# Sheet1_Filter.net
KiCad netlist of a schematic drawn in Altium Designer
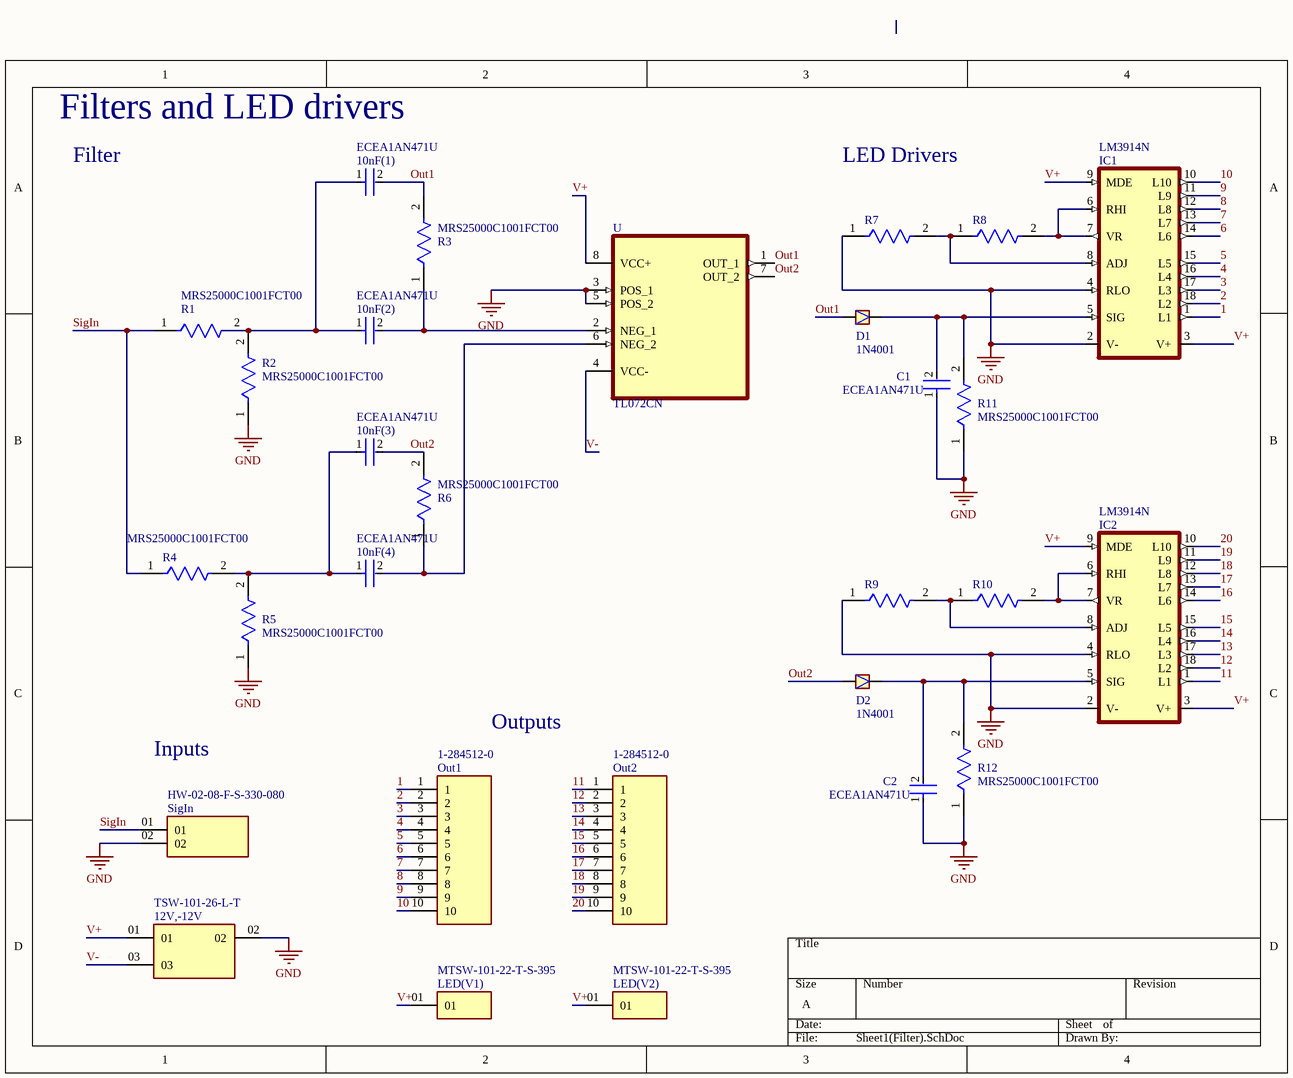
[diagram p0: Sheet1(Filter).SchDoc]

(export (version "E")
  (design (tool "Eeschema 10.0.6"))
  (components
    (comp (ref "10nF(1)")
      (value "ECEA1AN471U")
      (footprint "FP-RAD-TH-D_10_0_5-L_16_1-MFG")
      (description "Aluminum Electrolytic Capacitors (Radial Lead Type) 470uF ±20% 10V")
      (fields (field (name "TOLERANCE") "20%") (field (name "VOLTAGE") "10V"))
      (libsource (lib "Altium Content Vault") (part "02cd4be3c70576c341d710602a673aa"))
    )
    (comp (ref "10nF(2)")
      (value "ECEA1AN471U")
      (footprint "FP-RAD-TH-D_10_0_5-L_16_1-MFG")
      (description "Aluminum Electrolytic Capacitors (Radial Lead Type) 470uF ±20% 10V")
      (fields (field (name "TOLERANCE") "20%") (field (name "VOLTAGE") "10V"))
      (libsource (lib "Altium Content Vault") (part "02cd4be3c70576c341d710602a673aa"))
    )
    (comp (ref "10nF(3)")
      (value "ECEA1AN471U")
      (footprint "FP-RAD-TH-D_10_0_5-L_16_1-MFG")
      (description "Aluminum Electrolytic Capacitors (Radial Lead Type) 470uF ±20% 10V")
      (fields (field (name "TOLERANCE") "20%") (field (name "VOLTAGE") "10V"))
      (libsource (lib "Altium Content Vault") (part "02cd4be3c70576c341d710602a673aa"))
    )
    (comp (ref "10nF(4)")
      (value "ECEA1AN471U")
      (footprint "FP-RAD-TH-D_10_0_5-L_16_1-MFG")
      (description "Aluminum Electrolytic Capacitors (Radial Lead Type) 470uF ±20% 10V")
      (fields (field (name "TOLERANCE") "20%") (field (name "VOLTAGE") "10V"))
      (libsource (lib "Altium Content Vault") (part "02cd4be3c70576c341d710602a673aa"))
    )
    (comp (ref "12V,-12V")
      (value "TSW-101-26-L-T")
      (footprint "SAMTEC_TSW-101-26-L-T")
      (libsource (lib "TSW-101-26-L-T") (part "TSW-101-26-L-T"))
    )
    (comp (ref "C1")
      (value "ECEA1AN471U")
      (footprint "FP-RAD-TH-D_10_0_5-L_16_1-MFG")
      (description "Aluminum Electrolytic Capacitors (Radial Lead Type) 470uF ±20% 10V")
      (fields (field (name "TOLERANCE") "20%") (field (name "VOLTAGE") "10V"))
      (libsource (lib "Altium Content Vault") (part "02cd4be3c70576c341d710602a673aa"))
    )
    (comp (ref "C2")
      (value "ECEA1AN471U")
      (footprint "FP-RAD-TH-D_10_0_5-L_16_1-MFG")
      (description "Aluminum Electrolytic Capacitors (Radial Lead Type) 470uF ±20% 10V")
      (fields (field (name "TOLERANCE") "20%") (field (name "VOLTAGE") "10V"))
      (libsource (lib "Altium Content Vault") (part "02cd4be3c70576c341d710602a673aa"))
    )
    (comp (ref "D1")
      (value "1N4001")
      (footprint "DO41-10")
      (description "<B>DIODE</B><p> general purpose rectifier, 1 A")
      (fields (field (name "MP") "altium_native_batch"))
      (libsource (lib "1N4001") (part "1N4001"))
    )
    (comp (ref "D2")
      (value "1N4001")
      (footprint "DO41-10")
      (description "<B>DIODE</B><p> general purpose rectifier, 1 A")
      (fields (field (name "MP") "altium_native_batch"))
      (libsource (lib "1N4001") (part "1N4001"))
    )
    (comp (ref "IC1")
      (value "LM3914N")
      (footprint "DIL18")
      (description "LED Lighting Drivers")
      (fields (field (name "MF") "Texas Instruments"))
      (libsource (lib "LM3914N") (part "LM3914N"))
    )
    (comp (ref "IC2")
      (value "LM3914N")
      (footprint "DIL18")
      (description "LED Lighting Drivers")
      (fields (field (name "MF") "Texas Instruments"))
      (libsource (lib "LM3914N") (part "LM3914N"))
    )
    (comp (ref "LED(V1)")
      (value "MTSW-101-22-T-S-395")
      (footprint "SAMTEC_MTSW-101-22-T-S-395")
      (description "Connector Header Through Hole 1 position")
      (fields (field (name "MF") "Samtec"))
      (libsource (lib "MTSW-101-22-T-S-395") (part "MTSW-101-22-T-S-395"))
    )
    (comp (ref "LED(V2)")
      (value "MTSW-101-22-T-S-395")
      (footprint "SAMTEC_MTSW-101-22-T-S-395")
      (description "Connector Header Through Hole 1 position")
      (fields (field (name "MF") "Samtec"))
      (libsource (lib "MTSW-101-22-T-S-395") (part "MTSW-101-22-T-S-395"))
    )
    (comp (ref "Out1")
      (value "1-284512-0")
      (footprint "TE_1-284512-0")
      (description "10 POS TERMI-BLOK HDR 900 POLA")
      (fields (field (name "MF") "TE Connectivity"))
      (libsource (lib "1-284512-0") (part "1-284512-0"))
    )
    (comp (ref "Out2")
      (value "1-284512-0")
      (footprint "TE_1-284512-0")
      (description "10 POS TERMI-BLOK HDR 900 POLA")
      (fields (field (name "MF") "TE Connectivity"))
      (libsource (lib "1-284512-0") (part "1-284512-0"))
    )
    (comp (ref "R1")
      (value "MRS25000C1001FCT00")
      (footprint "FP-MRS25-MFG")
      (description "RES 1K OHM 0.6W 1% AXIAL")
      (fields (field (name "TOLERANCE") "1%"))
      (libsource (lib "Altium Content Vault") (part "1029c3af85768c4190bb7ad29bc67b5"))
    )
    (comp (ref "R2")
      (value "MRS25000C1001FCT00")
      (footprint "FP-MRS25-MFG")
      (description "RES 1K OHM 0.6W 1% AXIAL")
      (fields (field (name "TOLERANCE") "1%"))
      (libsource (lib "Altium Content Vault") (part "1029c3af85768c4190bb7ad29bc67b5"))
    )
    (comp (ref "R3")
      (value "MRS25000C1001FCT00")
      (footprint "FP-MRS25-MFG")
      (description "RES 1K OHM 0.6W 1% AXIAL")
      (fields (field (name "TOLERANCE") "1%"))
      (libsource (lib "Altium Content Vault") (part "1029c3af85768c4190bb7ad29bc67b5"))
    )
    (comp (ref "R4")
      (value "MRS25000C1001FCT00")
      (footprint "FP-MRS25-MFG")
      (description "RES 1K OHM 0.6W 1% AXIAL")
      (fields (field (name "TOLERANCE") "1%"))
      (libsource (lib "Altium Content Vault") (part "1029c3af85768c4190bb7ad29bc67b5"))
    )
    (comp (ref "R5")
      (value "MRS25000C1001FCT00")
      (footprint "FP-MRS25-MFG")
      (description "RES 1K OHM 0.6W 1% AXIAL")
      (fields (field (name "TOLERANCE") "1%"))
      (libsource (lib "Altium Content Vault") (part "1029c3af85768c4190bb7ad29bc67b5"))
    )
    (comp (ref "R6")
      (value "MRS25000C1001FCT00")
      (footprint "FP-MRS25-MFG")
      (description "RES 1K OHM 0.6W 1% AXIAL")
      (fields (field (name "TOLERANCE") "1%"))
      (libsource (lib "Altium Content Vault") (part "1029c3af85768c4190bb7ad29bc67b5"))
    )
    (comp (ref "R7")
      (value "MRS25000C1001FCT00")
      (footprint "FP-MRS25-MFG")
      (description "RES 1K OHM 0.6W 1% AXIAL")
      (fields (field (name "TOLERANCE") "1%"))
      (libsource (lib "Altium Content Vault") (part "1029c3af85768c4190bb7ad29bc67b5"))
    )
    (comp (ref "R8")
      (value "MRS25000C1001FCT00")
      (footprint "FP-MRS25-MFG")
      (description "RES 1K OHM 0.6W 1% AXIAL")
      (fields (field (name "TOLERANCE") "1%"))
      (libsource (lib "Altium Content Vault") (part "1029c3af85768c4190bb7ad29bc67b5"))
    )
    (comp (ref "R9")
      (value "MRS25000C1001FCT00")
      (footprint "FP-MRS25-MFG")
      (description "RES 1K OHM 0.6W 1% AXIAL")
      (fields (field (name "TOLERANCE") "1%"))
      (libsource (lib "Altium Content Vault") (part "1029c3af85768c4190bb7ad29bc67b5"))
    )
    (comp (ref "R10")
      (value "MRS25000C1001FCT00")
      (footprint "FP-MRS25-MFG")
      (description "RES 1K OHM 0.6W 1% AXIAL")
      (fields (field (name "TOLERANCE") "1%"))
      (libsource (lib "Altium Content Vault") (part "1029c3af85768c4190bb7ad29bc67b5"))
    )
    (comp (ref "R11")
      (value "MRS25000C1001FCT00")
      (footprint "FP-MRS25-MFG")
      (description "RES 1K OHM 0.6W 1% AXIAL")
      (fields (field (name "TOLERANCE") "1%"))
      (libsource (lib "Altium Content Vault") (part "1029c3af85768c4190bb7ad29bc67b5"))
    )
    (comp (ref "R12")
      (value "MRS25000C1001FCT00")
      (footprint "FP-MRS25-MFG")
      (description "RES 1K OHM 0.6W 1% AXIAL")
      (fields (field (name "TOLERANCE") "1%"))
      (libsource (lib "Altium Content Vault") (part "1029c3af85768c4190bb7ad29bc67b5"))
    )
    (comp (ref "SigIn")
      (value "HW-02-08-F-S-330-080")
      (footprint "SAMTEC_HW-02-08-F-S-330-080")
      (libsource (lib "HW-02-08-F-S-330-080") (part "HW-02-08-F-S-330-080"))
    )
    (comp (ref "U")
      (value "TL072CN")
      (footprint "DIP254P762X533-8")
      (description "J-FET Amplifier 2 Circuit 8-DIP")
      (fields (field (name "MF") "Texas Instruments"))
      (libsource (lib "TL072CN") (part "TL072CN"))
    )
  )
  (nets
    (net (code "1") (name "/1") (class "Default")
      (node (ref "IC1") (pin "1") (pinfunction "L1_1") (pintype "output"))
      (node (ref "Out1") (pin "1") (pinfunction "1_1") (pintype "passive"))
    )
    (net (code "2") (name "/2") (class "Default")
      (node (ref "IC1") (pin "18") (pinfunction "L2_18") (pintype "output"))
      (node (ref "Out1") (pin "2") (pinfunction "2_2") (pintype "passive"))
    )
    (net (code "3") (name "/3") (class "Default")
      (node (ref "IC1") (pin "17") (pinfunction "L3_17") (pintype "output"))
      (node (ref "Out1") (pin "3") (pinfunction "3_3") (pintype "passive"))
    )
    (net (code "4") (name "/4") (class "Default")
      (node (ref "IC1") (pin "16") (pinfunction "L4_16") (pintype "output"))
      (node (ref "Out1") (pin "4") (pinfunction "4_4") (pintype "passive"))
    )
    (net (code "5") (name "/5") (class "Default")
      (node (ref "IC1") (pin "15") (pinfunction "L5_15") (pintype "output"))
      (node (ref "Out1") (pin "5") (pinfunction "5_5") (pintype "passive"))
    )
    (net (code "6") (name "/6") (class "Default")
      (node (ref "IC1") (pin "14") (pinfunction "L6_14") (pintype "output"))
      (node (ref "Out1") (pin "6") (pinfunction "6_6") (pintype "passive"))
    )
    (net (code "7") (name "/7") (class "Default")
      (node (ref "IC1") (pin "13") (pinfunction "L7_13") (pintype "output"))
      (node (ref "Out1") (pin "7") (pinfunction "7_7") (pintype "passive"))
    )
    (net (code "8") (name "/8") (class "Default")
      (node (ref "IC1") (pin "12") (pinfunction "L8_12") (pintype "output"))
      (node (ref "Out1") (pin "8") (pinfunction "8_8") (pintype "passive"))
    )
    (net (code "9") (name "/9") (class "Default")
      (node (ref "IC1") (pin "11") (pinfunction "L9_11") (pintype "output"))
      (node (ref "Out1") (pin "9") (pinfunction "9_9") (pintype "passive"))
    )
    (net (code "10") (name "/10") (class "Default")
      (node (ref "IC1") (pin "10") (pinfunction "L10_10") (pintype "output"))
      (node (ref "Out1") (pin "10") (pinfunction "10_10") (pintype "passive"))
    )
    (net (code "11") (name "/11") (class "Default")
      (node (ref "IC2") (pin "1") (pinfunction "L1_1") (pintype "output"))
      (node (ref "Out2") (pin "1") (pinfunction "1_1") (pintype "passive"))
    )
    (net (code "12") (name "/12") (class "Default")
      (node (ref "IC2") (pin "18") (pinfunction "L2_18") (pintype "output"))
      (node (ref "Out2") (pin "2") (pinfunction "2_2") (pintype "passive"))
    )
    (net (code "13") (name "/13") (class "Default")
      (node (ref "IC2") (pin "17") (pinfunction "L3_17") (pintype "output"))
      (node (ref "Out2") (pin "3") (pinfunction "3_3") (pintype "passive"))
    )
    (net (code "14") (name "/14") (class "Default")
      (node (ref "IC2") (pin "16") (pinfunction "L4_16") (pintype "output"))
      (node (ref "Out2") (pin "4") (pinfunction "4_4") (pintype "passive"))
    )
    (net (code "15") (name "/15") (class "Default")
      (node (ref "IC2") (pin "15") (pinfunction "L5_15") (pintype "output"))
      (node (ref "Out2") (pin "5") (pinfunction "5_5") (pintype "passive"))
    )
    (net (code "16") (name "/16") (class "Default")
      (node (ref "IC2") (pin "14") (pinfunction "L6_14") (pintype "output"))
      (node (ref "Out2") (pin "6") (pinfunction "6_6") (pintype "passive"))
    )
    (net (code "17") (name "/17") (class "Default")
      (node (ref "IC2") (pin "13") (pinfunction "L7_13") (pintype "output"))
      (node (ref "Out2") (pin "7") (pinfunction "7_7") (pintype "passive"))
    )
    (net (code "18") (name "/18") (class "Default")
      (node (ref "IC2") (pin "12") (pinfunction "L8_12") (pintype "output"))
      (node (ref "Out2") (pin "8") (pinfunction "8_8") (pintype "passive"))
    )
    (net (code "19") (name "/19") (class "Default")
      (node (ref "IC2") (pin "11") (pinfunction "L9_11") (pintype "output"))
      (node (ref "Out2") (pin "9") (pinfunction "9_9") (pintype "passive"))
    )
    (net (code "20") (name "/20") (class "Default")
      (node (ref "IC2") (pin "10") (pinfunction "L10_10") (pintype "output"))
      (node (ref "Out2") (pin "10") (pinfunction "10_10") (pintype "passive"))
    )
    (net (code "21") (name "/Out1") (class "Default")
      (node (ref "10nF(1)") (pin "2") (pinfunction "2_2") (pintype "passive"))
      (node (ref "D1") (pin "A") (pinfunction "ANODE_A") (pintype "passive"))
      (node (ref "R3") (pin "2") (pinfunction "2_2") (pintype "passive"))
      (node (ref "U") (pin "1") (pinfunction "OUT_1_1") (pintype "output"))
    )
    (net (code "22") (name "/Out2") (class "Default")
      (node (ref "10nF(3)") (pin "2") (pinfunction "2_2") (pintype "passive"))
      (node (ref "D2") (pin "A") (pinfunction "ANODE_A") (pintype "passive"))
      (node (ref "R6") (pin "2") (pinfunction "2_2") (pintype "passive"))
      (node (ref "U") (pin "7") (pinfunction "OUT_2_7") (pintype "output"))
    )
    (net (code "23") (name "/SigIn") (class "Default")
      (node (ref "R1") (pin "1") (pinfunction "1_1") (pintype "passive"))
      (node (ref "R4") (pin "1") (pinfunction "1_1") (pintype "passive"))
      (node (ref "SigIn") (pin "01") (pinfunction "01_01") (pintype "passive"))
    )
    (net (code "24") (name "/V+") (class "Default")
      (node (ref "12V,-12V") (pin "01") (pinfunction "01_01") (pintype "passive"))
      (node (ref "IC1") (pin "3") (pinfunction "V+_3") (pintype "power_in"))
      (node (ref "IC1") (pin "9") (pinfunction "MDE_9") (pintype "input"))
      (node (ref "IC2") (pin "3") (pinfunction "V+_3") (pintype "power_in"))
      (node (ref "IC2") (pin "9") (pinfunction "MDE_9") (pintype "input"))
      (node (ref "LED(V1)") (pin "01") (pinfunction "01_01") (pintype "passive"))
      (node (ref "LED(V2)") (pin "01") (pinfunction "01_01") (pintype "passive"))
      (node (ref "U") (pin "8") (pinfunction "VCC+_8") (pintype "power_in"))
    )
    (net (code "25") (name "/V-") (class "Default")
      (node (ref "12V,-12V") (pin "03") (pinfunction "03_03") (pintype "passive"))
      (node (ref "U") (pin "4") (pinfunction "VCC-_4") (pintype "power_in"))
    )
    (net (code "26") (name "GND") (class "Default")
      (node (ref "12V,-12V") (pin "02") (pinfunction "02_02") (pintype "passive"))
      (node (ref "C1") (pin "1") (pinfunction "1_1") (pintype "passive"))
      (node (ref "C2") (pin "1") (pinfunction "1_1") (pintype "passive"))
      (node (ref "IC1") (pin "2") (pinfunction "V-_2") (pintype "power_in"))
      (node (ref "IC1") (pin "4") (pinfunction "RLO_4") (pintype "input"))
      (node (ref "IC2") (pin "2") (pinfunction "V-_2") (pintype "power_in"))
      (node (ref "IC2") (pin "4") (pinfunction "RLO_4") (pintype "input"))
      (node (ref "R11") (pin "1") (pinfunction "1_1") (pintype "passive"))
      (node (ref "R12") (pin "1") (pinfunction "1_1") (pintype "passive"))
      (node (ref "R2") (pin "1") (pinfunction "1_1") (pintype "passive"))
      (node (ref "R5") (pin "1") (pinfunction "1_1") (pintype "passive"))
      (node (ref "R7") (pin "1") (pinfunction "1_1") (pintype "passive"))
      (node (ref "R9") (pin "1") (pinfunction "1_1") (pintype "passive"))
      (node (ref "SigIn") (pin "02") (pinfunction "02_02") (pintype "passive"))
      (node (ref "U") (pin "3") (pinfunction "POS_1_3") (pintype "input"))
      (node (ref "U") (pin "5") (pinfunction "POS_2_5") (pintype "input"))
    )
    (net (code "27") (name "Net-(10nF(1)-Pad1)") (class "Default")
      (node (ref "10nF(1)") (pin "1") (pinfunction "1_1") (pintype "passive"))
      (node (ref "10nF(2)") (pin "1") (pinfunction "1_1") (pintype "passive"))
      (node (ref "R1") (pin "2") (pinfunction "2_2") (pintype "passive"))
      (node (ref "R2") (pin "2") (pinfunction "2_2") (pintype "passive"))
    )
    (net (code "28") (name "Net-(10nF(3)-Pad1)") (class "Default")
      (node (ref "10nF(3)") (pin "1") (pinfunction "1_1") (pintype "passive"))
      (node (ref "10nF(4)") (pin "1") (pinfunction "1_1") (pintype "passive"))
      (node (ref "R4") (pin "2") (pinfunction "2_2") (pintype "passive"))
      (node (ref "R5") (pin "2") (pinfunction "2_2") (pintype "passive"))
    )
    (net (code "29") (name "Net-(D1-CATHODE)") (class "Default")
      (node (ref "C1") (pin "2") (pinfunction "2_2") (pintype "passive"))
      (node (ref "D1") (pin "C") (pinfunction "CATHODE_C") (pintype "passive"))
      (node (ref "IC1") (pin "5") (pinfunction "SIG_5") (pintype "input"))
      (node (ref "R11") (pin "2") (pinfunction "2_2") (pintype "passive"))
    )
    (net (code "30") (name "Net-(D2-CATHODE)") (class "Default")
      (node (ref "C2") (pin "2") (pinfunction "2_2") (pintype "passive"))
      (node (ref "D2") (pin "C") (pinfunction "CATHODE_C") (pintype "passive"))
      (node (ref "IC2") (pin "5") (pinfunction "SIG_5") (pintype "input"))
      (node (ref "R12") (pin "2") (pinfunction "2_2") (pintype "passive"))
    )
    (net (code "31") (name "Net-(IC1-ADJ)") (class "Default")
      (node (ref "IC1") (pin "8") (pinfunction "ADJ_8") (pintype "input"))
      (node (ref "R7") (pin "2") (pinfunction "2_2") (pintype "passive"))
      (node (ref "R8") (pin "1") (pinfunction "1_1") (pintype "passive"))
    )
    (net (code "32") (name "Net-(IC1-RHI)") (class "Default")
      (node (ref "IC1") (pin "6") (pinfunction "RHI_6") (pintype "input"))
      (node (ref "IC1") (pin "7") (pinfunction "VR_7") (pintype "output"))
      (node (ref "R8") (pin "2") (pinfunction "2_2") (pintype "passive"))
    )
    (net (code "33") (name "Net-(IC2-ADJ)") (class "Default")
      (node (ref "IC2") (pin "8") (pinfunction "ADJ_8") (pintype "input"))
      (node (ref "R10") (pin "1") (pinfunction "1_1") (pintype "passive"))
      (node (ref "R9") (pin "2") (pinfunction "2_2") (pintype "passive"))
    )
    (net (code "34") (name "Net-(IC2-RHI)") (class "Default")
      (node (ref "IC2") (pin "6") (pinfunction "RHI_6") (pintype "input"))
      (node (ref "IC2") (pin "7") (pinfunction "VR_7") (pintype "output"))
      (node (ref "R10") (pin "2") (pinfunction "2_2") (pintype "passive"))
    )
    (net (code "35") (name "Net-(U-NEG_1)") (class "Default")
      (node (ref "10nF(2)") (pin "2") (pinfunction "2_2") (pintype "passive"))
      (node (ref "R3") (pin "1") (pinfunction "1_1") (pintype "passive"))
      (node (ref "U") (pin "2") (pinfunction "NEG_1_2") (pintype "input"))
    )
    (net (code "36") (name "Net-(U-NEG_2)") (class "Default")
      (node (ref "10nF(4)") (pin "2") (pinfunction "2_2") (pintype "passive"))
      (node (ref "R6") (pin "1") (pinfunction "1_1") (pintype "passive"))
      (node (ref "U") (pin "6") (pinfunction "NEG_2_6") (pintype "input"))
    )
  )
)
